# TEMP_MGT.net
KiCad netlist of a schematic drawn in Altium Designer
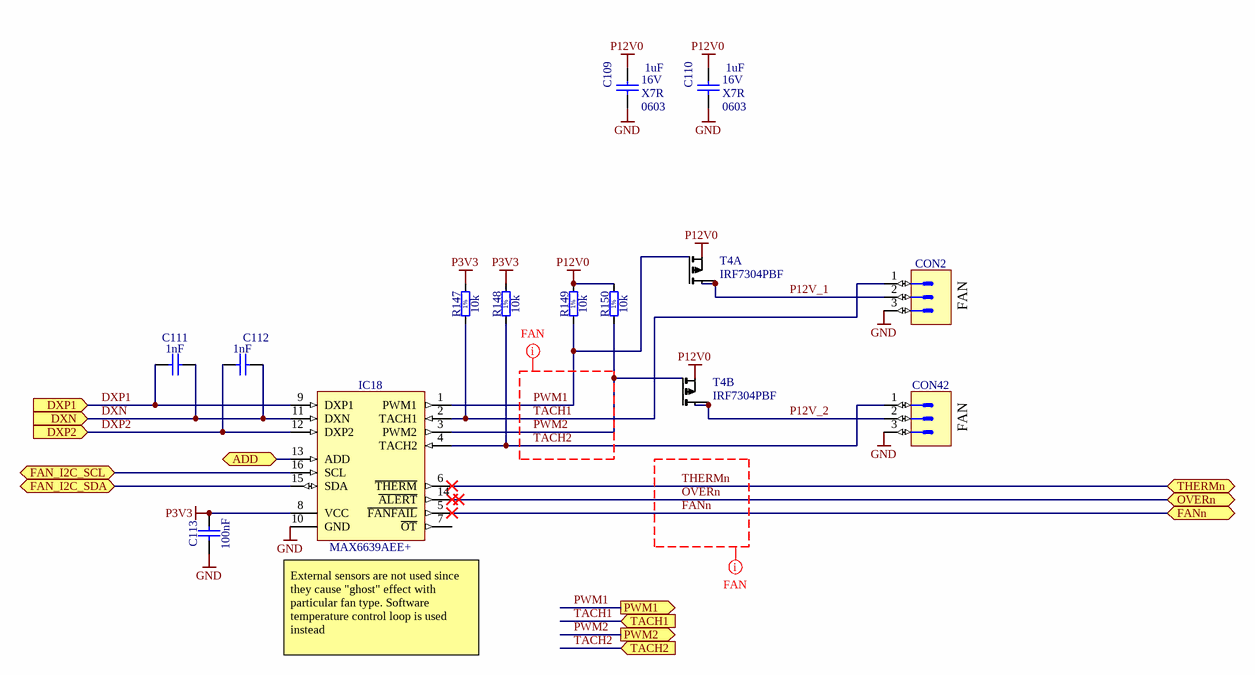
[diagram p0: TEMP_MGT.SchDoc]

(export (version "E")
  (design (tool "Eeschema 10.0.6"))
  (components
    (comp (ref "C109")
      (value "1uF")
      (footprint "CAPC1608X87N")
      (description "Non-polarised capacitor")
      (fields
        (field (name "PART NUMBER") "CC0603_1UF_16V_10%_X7R")
        (field (name "VOLTAGE") "16V")
        (field (name "TC") "X7R")
        (field (name "TOLERANCE") "±10%")
        (field (name "CASE") "0603")
        (field (name "AUTHOR") "CERN DEM JLC")
      )
      (libsource (lib "Capacitors") (part "Capacitor - non polarized"))
    )
    (comp (ref "C110")
      (value "1uF")
      (footprint "CAPC1608X87N")
      (description "Non-polarised capacitor")
      (fields
        (field (name "PART NUMBER") "CC0603_1UF_16V_10%_X7R")
        (field (name "VOLTAGE") "16V")
        (field (name "TC") "X7R")
        (field (name "TOLERANCE") "±10%")
        (field (name "CASE") "0603")
        (field (name "AUTHOR") "CERN DEM JLC")
      )
      (libsource (lib "Capacitors") (part "Capacitor - non polarized"))
    )
    (comp (ref "C111")
      (value "1nF")
      (footprint "CAPC1608X87N")
      (description "Non-polarised capacitor")
      (fields
        (field (name "PART NUMBER") "CC0603_1NF_50V_10%_X7R")
        (field (name "VOLTAGE") "50V")
        (field (name "AUTHOR") "CERN DEM JLC")
      )
      (libsource (lib "Capacitors") (part "Capacitor - non polarized"))
    )
    (comp (ref "C112")
      (value "1nF")
      (footprint "CAPC1608X87N")
      (description "Non-polarised capacitor")
      (fields
        (field (name "PART NUMBER") "CC0603_1NF_50V_10%_X7R")
        (field (name "VOLTAGE") "50V")
        (field (name "AUTHOR") "CERN DEM JLC")
      )
      (libsource (lib "Capacitors") (part "Capacitor - non polarized"))
    )
    (comp (ref "C113")
      (value "100nF")
      (footprint "CAPC1005X55N")
      (description "Non-polarised capacitor")
      (fields
        (field (name "PART NUMBER") "CC0402_100NF_16V_10%_X7R")
        (field (name "VOLTAGE") "16V")
        (field (name "AUTHOR") "CERN DEM JLC")
      )
      (libsource (lib "Capacitors") (part "Capacitor - non polarized"))
    )
    (comp (ref "CON2")
      (value "KK®")
      (footprint "MOLEX_22-05-7038")
      (description "Connector 3 Male")
      (fields
        (field (name "PART NUMBER") "MOLEX_22-05-7038")
        (field (name "MANUFACTURER") "MOLEX")
        (field (name "AUTHOR") "CERN DEM JLC")
      )
      (libsource (lib "Connectors") (part "Connector 3 Male"))
    )
    (comp (ref "CON42")
      (value "KK®")
      (footprint "MOLEX_22-05-7038")
      (description "Connector 3 Male")
      (fields
        (field (name "PART NUMBER") "MOLEX_22-05-7038")
        (field (name "MANUFACTURER") "MOLEX")
        (field (name "AUTHOR") "CERN DEM JLC")
      )
      (libsource (lib "Connectors") (part "Connector 3 Male"))
    )
    (comp (ref "IC18")
      (value "MAX6639AEE+")
      (footprint "SOP63P600X175-16N")
      (description "2-Channel Temperature Monitor with Dual, Automatic, PWM Fan-Speed Controller")
      (fields (field (name "MANUFACTURER") "MAXIM") (field (name "AUTHOR") "CERN DEM JLC"))
      (libsource (lib "ICs And Semiconductors") (part "MAX6639AEE+"))
    )
    (comp (ref "R147")
      (value "10k")
      (footprint "RESC1005X40N")
      (description "Resistor - 1%")
      (fields
        (field (name "PART NUMBER") "R0402_10K_1%_0.0625W_100PPM")
        (field (name "POWER") "0.0625W")
        (field (name "AUTHOR") "CERN DEM JLC")
      )
      (libsource (lib "Resistors") (part "Resistor - 1%"))
    )
    (comp (ref "R148")
      (value "10k")
      (footprint "RESC1005X40N")
      (description "Resistor - 1%")
      (fields
        (field (name "PART NUMBER") "R0402_10K_1%_0.0625W_100PPM")
        (field (name "POWER") "0.0625W")
        (field (name "AUTHOR") "CERN DEM JLC")
      )
      (libsource (lib "Resistors") (part "Resistor - 1%"))
    )
    (comp (ref "R149")
      (value "10k")
      (footprint "RESC1005X40N")
      (description "Resistor - 1%")
      (fields
        (field (name "PART NUMBER") "R0402_10K_1%_0.0625W_100PPM")
        (field (name "POWER") "0.0625W")
        (field (name "AUTHOR") "CERN DEM JLC")
      )
      (libsource (lib "Resistors") (part "Resistor - 1%"))
    )
    (comp (ref "R150")
      (value "10k")
      (footprint "RESC1005X40N")
      (description "Resistor - 1%")
      (fields
        (field (name "PART NUMBER") "R0402_10K_1%_0.0625W_100PPM")
        (field (name "POWER") "0.0625W")
        (field (name "AUTHOR") "CERN DEM JLC")
      )
      (libsource (lib "Resistors") (part "Resistor - 1%"))
    )
    (comp (ref "T4")
      (value "IRF7304PBF")
      (footprint "so-8")
      (description "dual PMOS   20V 4,3A 2,0W 0,09R")
      (libsource (lib "LIBRARY_SCH") (part "Q_IRF7304"))
    )
  )
  (nets
    (net (code "1") (name "/ADD") (class "Default")
      (node (ref "IC18") (pin "13") (pinfunction "ADD_13") (pintype "input"))
    )
    (net (code "2") (name "/DXN") (class "Default")
      (node (ref "C111") (pin "1") (pinfunction "1_1") (pintype "passive"))
      (node (ref "C112") (pin "1") (pinfunction "1_1") (pintype "passive"))
      (node (ref "IC18") (pin "11") (pinfunction "DXN_11") (pintype "input"))
    )
    (net (code "3") (name "/DXP1") (class "Default")
      (node (ref "C111") (pin "2") (pinfunction "2_2") (pintype "passive"))
      (node (ref "IC18") (pin "9") (pinfunction "DXP1_9") (pintype "input"))
    )
    (net (code "4") (name "/DXP2") (class "Default")
      (node (ref "C112") (pin "2") (pinfunction "2_2") (pintype "passive"))
      (node (ref "IC18") (pin "12") (pinfunction "DXP2_12") (pintype "input"))
    )
    (net (code "5") (name "/FAN_I2C_SCL") (class "Default")
      (node (ref "IC18") (pin "16") (pinfunction "SCL_16") (pintype "input"))
    )
    (net (code "6") (name "/FAN_I2C_SDA") (class "Default")
      (node (ref "IC18") (pin "15") (pinfunction "SDA_15") (pintype "bidirectional"))
    )
    (net (code "7") (name "/FANn") (class "Default")
      (node (ref "IC18") (pin "5") (pinfunction "~{FANFAIL}_5") (pintype "output+no_connect"))
    )
    (net (code "8") (name "/OVERn") (class "Default")
      (node (ref "IC18") (pin "14") (pinfunction "~{ALERT}_14") (pintype "output+no_connect"))
    )
    (net (code "9") (name "/P12V_1") (class "Default")
      (node (ref "CON2") (pin "2") (pinfunction "2_2") (pintype "bidirectional"))
      (node (ref "T4") (pin "7") (pinfunction "D1_7") (pintype "passive"))
      (node (ref "T4") (pin "8") (pinfunction "D1_8") (pintype "passive"))
    )
    (net (code "10") (name "/P12V_2") (class "Default")
      (node (ref "CON42") (pin "2") (pinfunction "2_2") (pintype "bidirectional"))
      (node (ref "T4") (pin "5") (pinfunction "D2_5") (pintype "passive"))
      (node (ref "T4") (pin "6") (pinfunction "D2_6") (pintype "passive"))
    )
    (net (code "11") (name "/PWM1") (class "Default")
      (node (ref "IC18") (pin "1") (pinfunction "PWM1_1") (pintype "output"))
      (node (ref "R149") (pin "1") (pinfunction "1_1") (pintype "passive"))
      (node (ref "T4") (pin "2") (pinfunction "G1_2") (pintype "input"))
    )
    (net (code "12") (name "/PWM2") (class "Default")
      (node (ref "IC18") (pin "3") (pinfunction "PWM2_3") (pintype "output"))
      (node (ref "R150") (pin "1") (pinfunction "1_1") (pintype "passive"))
      (node (ref "T4") (pin "4") (pinfunction "G2_4") (pintype "input"))
    )
    (net (code "13") (name "/TACH1") (class "Default")
      (node (ref "CON2") (pin "1") (pinfunction "1_1") (pintype "bidirectional"))
      (node (ref "IC18") (pin "2") (pinfunction "TACH1_2") (pintype "input"))
      (node (ref "R147") (pin "1") (pinfunction "1_1") (pintype "passive"))
    )
    (net (code "14") (name "/TACH2") (class "Default")
      (node (ref "CON42") (pin "1") (pinfunction "1_1") (pintype "bidirectional"))
      (node (ref "IC18") (pin "4") (pinfunction "TACH2_4") (pintype "input"))
      (node (ref "R148") (pin "1") (pinfunction "1_1") (pintype "passive"))
    )
    (net (code "15") (name "/THERMn") (class "Default")
      (node (ref "IC18") (pin "6") (pinfunction "~{THERM}_6") (pintype "output+no_connect"))
    )
    (net (code "16") (name "GND") (class "Default")
      (node (ref "C109") (pin "1") (pinfunction "1_1") (pintype "passive"))
      (node (ref "C110") (pin "1") (pinfunction "1_1") (pintype "passive"))
      (node (ref "C113") (pin "1") (pinfunction "1_1") (pintype "passive"))
      (node (ref "CON2") (pin "3") (pinfunction "3_3") (pintype "bidirectional"))
      (node (ref "CON42") (pin "3") (pinfunction "3_3") (pintype "bidirectional"))
      (node (ref "IC18") (pin "10") (pinfunction "GND_10") (pintype "power_in"))
    )
    (net (code "17") (name "P3V3") (class "Default")
      (node (ref "C113") (pin "2") (pinfunction "2_2") (pintype "passive"))
      (node (ref "IC18") (pin "8") (pinfunction "VCC_8") (pintype "power_in"))
      (node (ref "R147") (pin "2") (pinfunction "2_2") (pintype "passive"))
      (node (ref "R148") (pin "2") (pinfunction "2_2") (pintype "passive"))
    )
    (net (code "18") (name "P12V0") (class "Default")
      (node (ref "C109") (pin "2") (pinfunction "2_2") (pintype "passive"))
      (node (ref "C110") (pin "2") (pinfunction "2_2") (pintype "passive"))
      (node (ref "R149") (pin "2") (pinfunction "2_2") (pintype "passive"))
      (node (ref "R150") (pin "2") (pinfunction "2_2") (pintype "passive"))
      (node (ref "T4") (pin "1") (pinfunction "S1_1") (pintype "passive"))
      (node (ref "T4") (pin "3") (pinfunction "S2_3") (pintype "passive"))
    )
    (net (code "19") (name "unconnected-(IC18-~{OT}-Pad7)") (class "Default")
      (node (ref "IC18") (pin "7") (pinfunction "~{OT}_7") (pintype "output"))
    )
  )
)
